# tc_tp6_ej3.net
KiCad netlist of a schematic drawn in Altium Designer
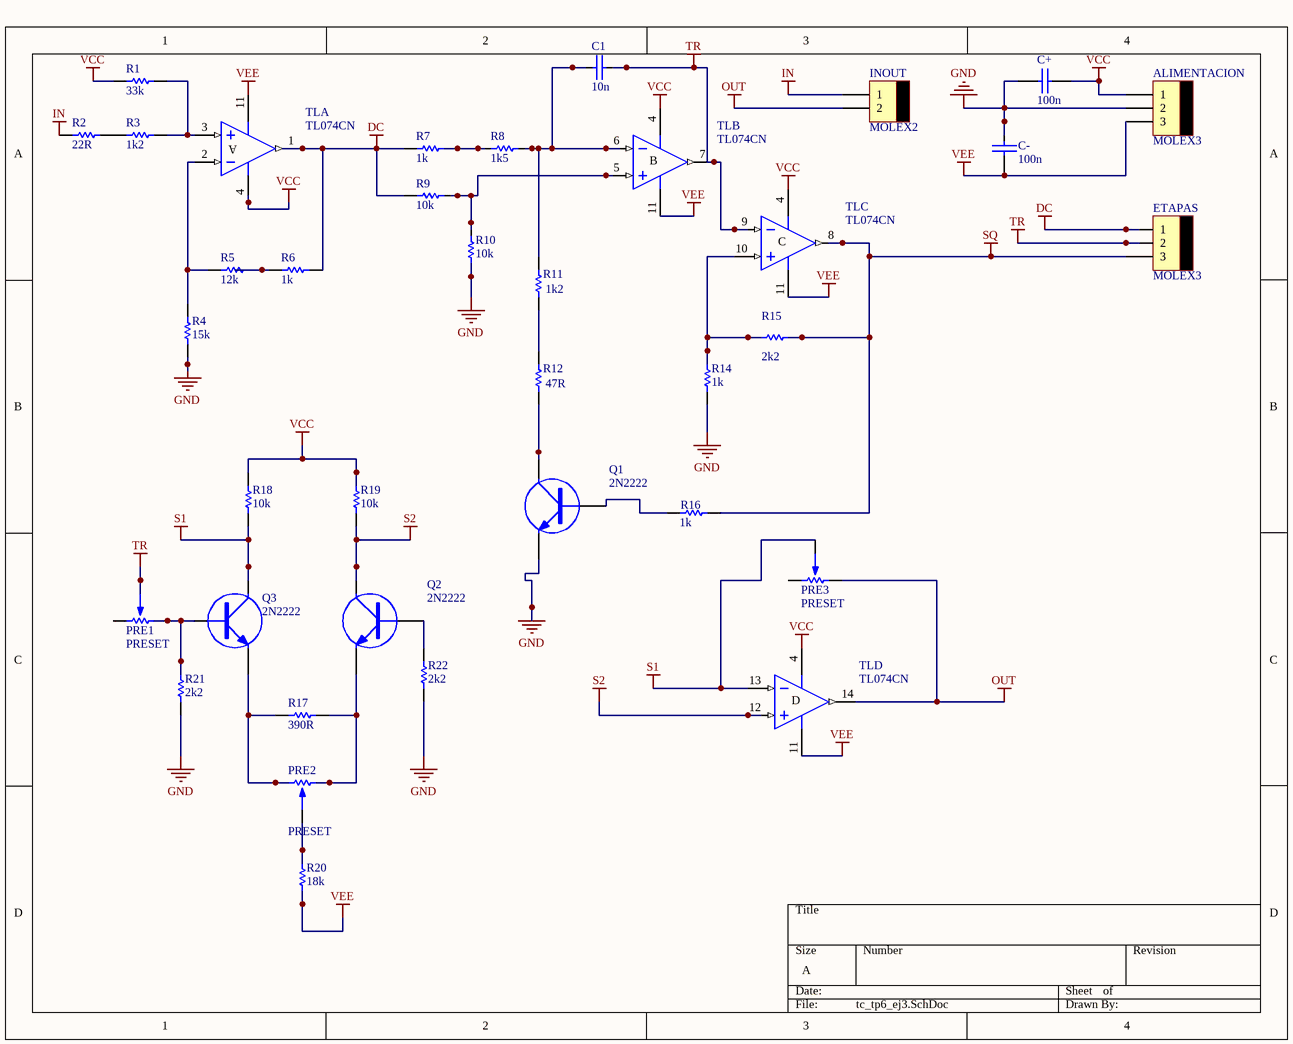
[diagram p0: tc_tp6_ej3.SchDoc]

(export (version "E")
  (design (tool "Eeschema 10.0.6"))
  (components
    (comp (ref "ALIMENTACION")
      (value "MOLEX3")
      (footprint "MOLEX3")
      (libsource (lib "LIBEBAL") (part "MOLEX3"))
    )
    (comp (ref "C+") (value "100n") (footprint "CAP200") (libsource (lib "LIBEBAL") (part "CAP")))
    (comp (ref "C-") (value "100n") (footprint "CAP200") (libsource (lib "LIBEBAL") (part "CAP")))
    (comp (ref "C1") (value "10n") (footprint "CAP200") (libsource (lib "LIBEBAL") (part "CAP")))
    (comp (ref "ETAPAS") (value "MOLEX3") (footprint "MOLEX3") (libsource (lib "LIBEBAL") (part "MOLEX3")))
    (comp (ref "INOUT") (value "MOLEX2") (footprint "MOLEX2") (libsource (lib "LIBEBAL") (part "MOLEX2")))
    (comp (ref "PRE1") (value "PRESET") (footprint "PRESET V") (libsource (lib "LIBEBAL") (part "PRESET")))
    (comp (ref "PRE2") (value "PRESET") (footprint "PRESET V") (libsource (lib "LIBEBAL") (part "PRESET")))
    (comp (ref "PRE3") (value "PRESET") (footprint "PRESET V") (libsource (lib "LIBEBAL") (part "PRESET")))
    (comp (ref "Q1") (value "2N2222") (footprint "TO92") (libsource (lib "LIBEBAL") (part "2N2222")))
    (comp (ref "Q2") (value "2N2222") (footprint "TO92") (libsource (lib "LIBEBAL") (part "2N2222")))
    (comp (ref "Q3") (value "2N2222") (footprint "TO92") (libsource (lib "LIBEBAL") (part "2N2222")))
    (comp (ref "R1") (value "33k") (footprint "RES400") (libsource (lib "LIBEBAL") (part "RES")))
    (comp (ref "R2") (value "22R") (footprint "RES400") (libsource (lib "LIBEBAL") (part "RES")))
    (comp (ref "R3") (value "1k2") (footprint "RES400") (libsource (lib "LIBEBAL") (part "RES")))
    (comp (ref "R4") (value "15k") (footprint "RES400") (libsource (lib "LIBEBAL") (part "RES")))
    (comp (ref "R5") (value "12k") (footprint "RES400") (libsource (lib "LIBEBAL") (part "RES")))
    (comp (ref "R6") (value "1k") (footprint "RES400") (libsource (lib "LIBEBAL") (part "RES")))
    (comp (ref "R7") (value "1k") (footprint "RES400") (libsource (lib "LIBEBAL") (part "RES")))
    (comp (ref "R8") (value "1k5") (footprint "RES400") (libsource (lib "LIBEBAL") (part "RES")))
    (comp (ref "R9") (value "10k") (footprint "RES400") (libsource (lib "LIBEBAL") (part "RES")))
    (comp (ref "R10") (value "10k") (footprint "RES400") (libsource (lib "LIBEBAL") (part "RES")))
    (comp (ref "R11") (value "1k2") (footprint "RES400") (libsource (lib "LIBEBAL") (part "RES")))
    (comp (ref "R12") (value "47R") (footprint "RES400") (libsource (lib "LIBEBAL") (part "RES")))
    (comp (ref "R14") (value "1k") (footprint "RES400") (libsource (lib "LIBEBAL") (part "RES")))
    (comp (ref "R15") (value "2k2") (footprint "RES400") (libsource (lib "LIBEBAL") (part "RES")))
    (comp (ref "R16") (value "1k") (footprint "RES400") (libsource (lib "LIBEBAL") (part "RES")))
    (comp (ref "R17") (value "390R") (footprint "RES400") (libsource (lib "LIBEBAL") (part "RES")))
    (comp (ref "R18") (value "10k") (footprint "RES400") (libsource (lib "LIBEBAL") (part "RES")))
    (comp (ref "R19") (value "10k") (footprint "RES400") (libsource (lib "LIBEBAL") (part "RES")))
    (comp (ref "R20") (value "18k") (footprint "RES400") (libsource (lib "LIBEBAL") (part "RES")))
    (comp (ref "R21") (value "2k2") (footprint "RES400") (libsource (lib "LIBEBAL") (part "RES")))
    (comp (ref "R22") (value "2k2") (footprint "RES400") (libsource (lib "LIBEBAL") (part "RES")))
    (comp (ref "TL")
      (value "TL074CN")
      (footprint "DIP14")
      (description "Low-Noise J-FET Quad Operational Amplifier")
      (fields (field (name "PUBLISHER") "Altium Limited"))
      (libsource (lib "ST Operational Amplifier") (part "TL074CN"))
    )
  )
  (nets
    (net (code "1") (name "DC") (class "Default")
      (node (ref "ETAPAS") (pin "1") (pinfunction "1_1") (pintype "passive"))
      (node (ref "R6") (pin "1") (pinfunction "1_1") (pintype "passive"))
      (node (ref "R7") (pin "2") (pinfunction "2_2") (pintype "passive"))
      (node (ref "R9") (pin "1") (pinfunction "1_1") (pintype "passive"))
      (node (ref "TL") (pin "1") (pinfunction "OUT_1") (pintype "output"))
    )
    (net (code "2") (name "GND") (class "Default")
      (node (ref "ALIMENTACION") (pin "2") (pinfunction "2_2") (pintype "passive"))
      (node (ref "C+") (pin "1") (pinfunction "1_1") (pintype "passive"))
      (node (ref "C-") (pin "2") (pinfunction "2_2") (pintype "passive"))
      (node (ref "Q1") (pin "2") (pinfunction "E_2") (pintype "passive"))
      (node (ref "R10") (pin "1") (pinfunction "1_1") (pintype "passive"))
      (node (ref "R14") (pin "1") (pinfunction "1_1") (pintype "passive"))
      (node (ref "R21") (pin "1") (pinfunction "1_1") (pintype "passive"))
      (node (ref "R22") (pin "1") (pinfunction "1_1") (pintype "passive"))
      (node (ref "R4") (pin "1") (pinfunction "1_1") (pintype "passive"))
    )
    (net (code "3") (name "IN") (class "Default")
      (node (ref "INOUT") (pin "1") (pinfunction "1_1") (pintype "passive"))
      (node (ref "R2") (pin "1") (pinfunction "1_1") (pintype "passive"))
    )
    (net (code "4") (name "Net-(PRE2-Pad2)") (class "Default")
      (node (ref "PRE2") (pin "2") (pinfunction "2_2") (pintype "passive"))
      (node (ref "R20") (pin "2") (pinfunction "2_2") (pintype "passive"))
    )
    (net (code "5") (name "Net-(Q1-B)") (class "Default")
      (node (ref "Q1") (pin "1") (pinfunction "B_1") (pintype "passive"))
      (node (ref "R16") (pin "2") (pinfunction "2_2") (pintype "passive"))
    )
    (net (code "6") (name "Net-(Q1-C)") (class "Default")
      (node (ref "Q1") (pin "3") (pinfunction "C_3") (pintype "passive"))
      (node (ref "R12") (pin "1") (pinfunction "1_1") (pintype "passive"))
    )
    (net (code "7") (name "Net-(Q2-B)") (class "Default")
      (node (ref "Q2") (pin "1") (pinfunction "B_1") (pintype "passive"))
      (node (ref "R22") (pin "2") (pinfunction "2_2") (pintype "passive"))
    )
    (net (code "8") (name "Net-(Q2-E)") (class "Default")
      (node (ref "PRE2") (pin "1") (pinfunction "1_1") (pintype "passive"))
      (node (ref "Q2") (pin "2") (pinfunction "E_2") (pintype "passive"))
      (node (ref "R17") (pin "2") (pinfunction "2_2") (pintype "passive"))
    )
    (net (code "9") (name "Net-(Q3-B)") (class "Default")
      (node (ref "PRE1") (pin "3") (pinfunction "3_3") (pintype "passive"))
      (node (ref "Q3") (pin "1") (pinfunction "B_1") (pintype "passive"))
      (node (ref "R21") (pin "2") (pinfunction "2_2") (pintype "passive"))
    )
    (net (code "10") (name "Net-(Q3-E)") (class "Default")
      (node (ref "PRE2") (pin "3") (pinfunction "3_3") (pintype "passive"))
      (node (ref "Q3") (pin "2") (pinfunction "E_2") (pintype "passive"))
      (node (ref "R17") (pin "1") (pinfunction "1_1") (pintype "passive"))
    )
    (net (code "11") (name "Net-(R2-Pad2)") (class "Default")
      (node (ref "R2") (pin "2") (pinfunction "2_2") (pintype "passive"))
      (node (ref "R3") (pin "1") (pinfunction "1_1") (pintype "passive"))
    )
    (net (code "12") (name "Net-(R5-Pad1)") (class "Default")
      (node (ref "R5") (pin "1") (pinfunction "1_1") (pintype "passive"))
      (node (ref "R6") (pin "2") (pinfunction "2_2") (pintype "passive"))
    )
    (net (code "13") (name "Net-(R7-Pad1)") (class "Default")
      (node (ref "R7") (pin "1") (pinfunction "1_1") (pintype "passive"))
      (node (ref "R8") (pin "2") (pinfunction "2_2") (pintype "passive"))
    )
    (net (code "14") (name "Net-(R11-Pad1)") (class "Default")
      (node (ref "R11") (pin "1") (pinfunction "1_1") (pintype "passive"))
      (node (ref "R12") (pin "2") (pinfunction "2_2") (pintype "passive"))
    )
    (net (code "15") (name "Net-(TLA-IN+)") (class "Default")
      (node (ref "R1") (pin "2") (pinfunction "2_2") (pintype "passive"))
      (node (ref "R3") (pin "2") (pinfunction "2_2") (pintype "passive"))
      (node (ref "TL") (pin "3") (pinfunction "IN+_3") (pintype "input"))
    )
    (net (code "16") (name "Net-(TLA-IN-)") (class "Default")
      (node (ref "R4") (pin "2") (pinfunction "2_2") (pintype "passive"))
      (node (ref "R5") (pin "2") (pinfunction "2_2") (pintype "passive"))
      (node (ref "TL") (pin "2") (pinfunction "IN-_2") (pintype "input"))
    )
    (net (code "17") (name "Net-(TLB-IN+)") (class "Default")
      (node (ref "R10") (pin "2") (pinfunction "2_2") (pintype "passive"))
      (node (ref "R9") (pin "2") (pinfunction "2_2") (pintype "passive"))
      (node (ref "TL") (pin "5") (pinfunction "IN+_5") (pintype "input"))
    )
    (net (code "18") (name "Net-(TLB-IN-)") (class "Default")
      (node (ref "C1") (pin "1") (pinfunction "1_1") (pintype "passive"))
      (node (ref "R11") (pin "2") (pinfunction "2_2") (pintype "passive"))
      (node (ref "R8") (pin "1") (pinfunction "1_1") (pintype "passive"))
      (node (ref "TL") (pin "6") (pinfunction "IN-_6") (pintype "input"))
    )
    (net (code "19") (name "Net-(TLC-IN+)") (class "Default")
      (node (ref "R14") (pin "2") (pinfunction "2_2") (pintype "passive"))
      (node (ref "R15") (pin "2") (pinfunction "2_2") (pintype "passive"))
      (node (ref "TL") (pin "10") (pinfunction "IN+_10") (pintype "input"))
    )
    (net (code "20") (name "OUT") (class "Default")
      (node (ref "INOUT") (pin "2") (pinfunction "2_2") (pintype "passive"))
      (node (ref "PRE3") (pin "3") (pinfunction "3_3") (pintype "passive"))
      (node (ref "TL") (pin "14") (pinfunction "OUT_14") (pintype "output"))
    )
    (net (code "21") (name "S1") (class "Default")
      (node (ref "PRE3") (pin "2") (pinfunction "2_2") (pintype "passive"))
      (node (ref "Q3") (pin "3") (pinfunction "C_3") (pintype "passive"))
      (node (ref "R18") (pin "1") (pinfunction "1_1") (pintype "passive"))
      (node (ref "TL") (pin "13") (pinfunction "IN-_13") (pintype "input"))
    )
    (net (code "22") (name "S2") (class "Default")
      (node (ref "Q2") (pin "3") (pinfunction "C_3") (pintype "passive"))
      (node (ref "R19") (pin "1") (pinfunction "1_1") (pintype "passive"))
      (node (ref "TL") (pin "12") (pinfunction "IN+_12") (pintype "input"))
    )
    (net (code "23") (name "SQ") (class "Default")
      (node (ref "ETAPAS") (pin "3") (pinfunction "3_3") (pintype "passive"))
      (node (ref "R15") (pin "1") (pinfunction "1_1") (pintype "passive"))
      (node (ref "R16") (pin "1") (pinfunction "1_1") (pintype "passive"))
      (node (ref "TL") (pin "8") (pinfunction "OUT_8") (pintype "output"))
    )
    (net (code "24") (name "TR") (class "Default")
      (node (ref "C1") (pin "2") (pinfunction "2_2") (pintype "passive"))
      (node (ref "ETAPAS") (pin "2") (pinfunction "2_2") (pintype "passive"))
      (node (ref "PRE1") (pin "2") (pinfunction "2_2") (pintype "passive"))
      (node (ref "TL") (pin "7") (pinfunction "OUT_7") (pintype "output"))
      (node (ref "TL") (pin "9") (pinfunction "IN-_9") (pintype "input"))
    )
    (net (code "25") (name "VCC") (class "Default")
      (node (ref "ALIMENTACION") (pin "1") (pinfunction "1_1") (pintype "passive"))
      (node (ref "C+") (pin "2") (pinfunction "2_2") (pintype "passive"))
      (node (ref "R1") (pin "1") (pinfunction "1_1") (pintype "passive"))
      (node (ref "R18") (pin "2") (pinfunction "2_2") (pintype "passive"))
      (node (ref "R19") (pin "2") (pinfunction "2_2") (pintype "passive"))
      (node (ref "TL") (pin "4") (pinfunction "V+_4") (pintype "power_in"))
    )
    (net (code "26") (name "VEE") (class "Default")
      (node (ref "ALIMENTACION") (pin "3") (pinfunction "3_3") (pintype "passive"))
      (node (ref "C-") (pin "1") (pinfunction "1_1") (pintype "passive"))
      (node (ref "R20") (pin "1") (pinfunction "1_1") (pintype "passive"))
      (node (ref "TL") (pin "11") (pinfunction "V-_11") (pintype "power_in"))
    )
    (net (code "27") (name "unconnected-(PRE1-Pad1)") (class "Default")
      (node (ref "PRE1") (pin "1") (pinfunction "1_1") (pintype "passive"))
    )
    (net (code "28") (name "unconnected-(PRE3-Pad1)") (class "Default")
      (node (ref "PRE3") (pin "1") (pinfunction "1_1") (pintype "passive"))
    )
  )
)
